# nes_controller_v2_0.net
KiCad netlist of a schematic drawn in EAGLE
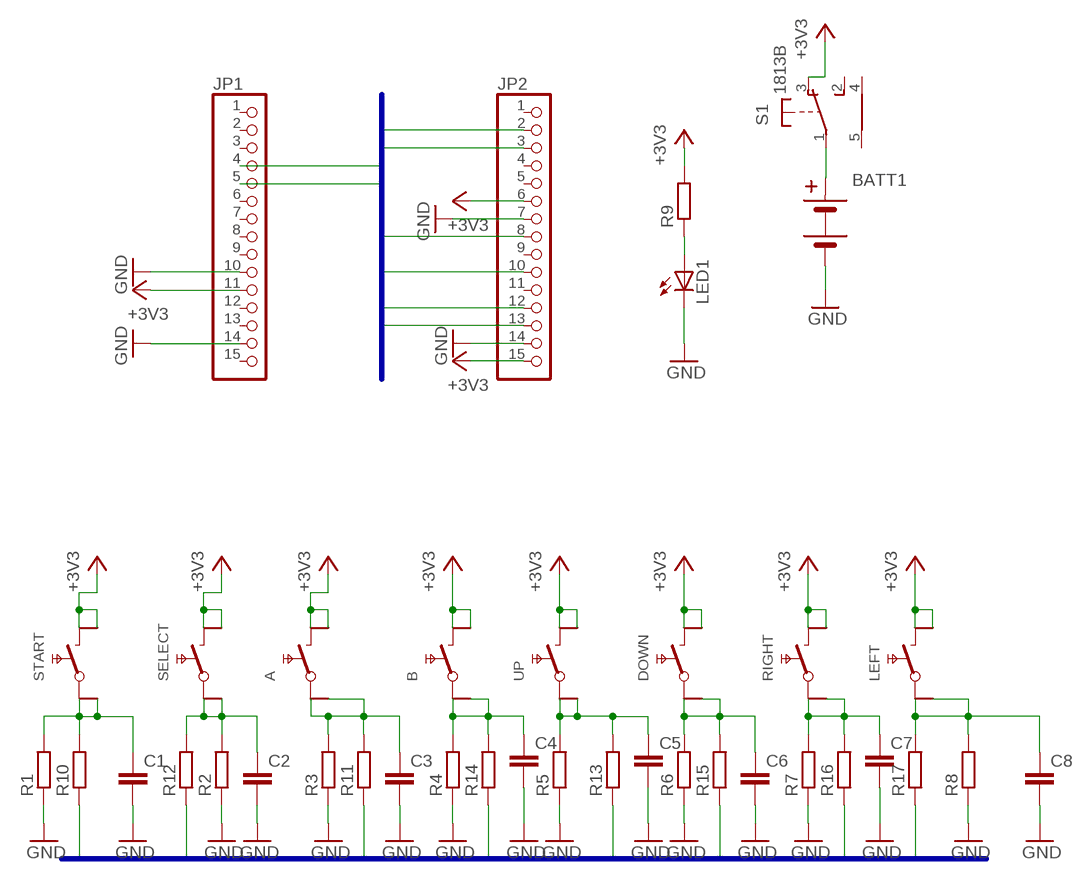
[diagram p0: schematic, sheet 1]

(export (version "E")
  (design (tool "Eeschema 10.0.6"))
  (components
    (comp (ref "A")
      (value "SMDTAST")
      (footprint "eagle-import:SMDTAST")
      (libsource (lib "eagle-import") (part "SMDTAST"))
    )
    (comp (ref "B")
      (value "SMDTAST")
      (footprint "eagle-import:SMDTAST")
      (libsource (lib "eagle-import") (part "SMDTAST"))
    )
    (comp (ref "BATT1")
      (value "BATTERIEHALTER_2X_AAA")
      (footprint "eagle-import:BATTERIEHALTER")
      (libsource (lib "eagle-import") (part "BATTERIEHALTER_2X_AAA"))
    )
    (comp (ref "C1")
      (value "C-EUC0805K")
      (footprint "eagle-import:C0805K")
      (libsource (lib "eagle-import") (part "C-EUC0805K"))
    )
    (comp (ref "C2")
      (value "C-EUC0805K")
      (footprint "eagle-import:C0805K")
      (libsource (lib "eagle-import") (part "C-EUC0805K"))
    )
    (comp (ref "C3")
      (value "C-EUC0805K")
      (footprint "eagle-import:C0805K")
      (libsource (lib "eagle-import") (part "C-EUC0805K"))
    )
    (comp (ref "C4")
      (value "C-EUC0805K")
      (footprint "eagle-import:C0805K")
      (libsource (lib "eagle-import") (part "C-EUC0805K"))
    )
    (comp (ref "C5")
      (value "C-EUC0805K")
      (footprint "eagle-import:C0805K")
      (libsource (lib "eagle-import") (part "C-EUC0805K"))
    )
    (comp (ref "C6")
      (value "C-EUC0805K")
      (footprint "eagle-import:C0805K")
      (libsource (lib "eagle-import") (part "C-EUC0805K"))
    )
    (comp (ref "C7")
      (value "C-EUC0805K")
      (footprint "eagle-import:C0805K")
      (libsource (lib "eagle-import") (part "C-EUC0805K"))
    )
    (comp (ref "C8")
      (value "C-EUC0805K")
      (footprint "eagle-import:C0805K")
      (libsource (lib "eagle-import") (part "C-EUC0805K"))
    )
    (comp (ref "DOWN")
      (value "SMDTAST")
      (footprint "eagle-import:SMDTAST")
      (libsource (lib "eagle-import") (part "SMDTAST"))
    )
    (comp (ref "JP1")
      (value "PINHD-1X15")
      (footprint "eagle-import:1X15")
      (libsource (lib "eagle-import") (part "PINHD-1X15"))
    )
    (comp (ref "JP2")
      (value "PINHD-1X15")
      (footprint "eagle-import:1X15")
      (libsource (lib "eagle-import") (part "PINHD-1X15"))
    )
    (comp (ref "LED1")
      (value "LED3MM")
      (footprint "eagle-import:LED3MM")
      (libsource (lib "eagle-import") (part "LED3MM"))
    )
    (comp (ref "LEFT")
      (value "SMDTAST")
      (footprint "eagle-import:SMDTAST")
      (libsource (lib "eagle-import") (part "SMDTAST"))
    )
    (comp (ref "R1")
      (value "R-EU_R1206")
      (footprint "eagle-import:R1206")
      (libsource (lib "eagle-import") (part "R-EU_R1206"))
    )
    (comp (ref "R2")
      (value "R-EU_R1206")
      (footprint "eagle-import:R1206")
      (libsource (lib "eagle-import") (part "R-EU_R1206"))
    )
    (comp (ref "R3")
      (value "R-EU_R1206")
      (footprint "eagle-import:R1206")
      (libsource (lib "eagle-import") (part "R-EU_R1206"))
    )
    (comp (ref "R4")
      (value "R-EU_R1206")
      (footprint "eagle-import:R1206")
      (libsource (lib "eagle-import") (part "R-EU_R1206"))
    )
    (comp (ref "R5")
      (value "R-EU_R1206")
      (footprint "eagle-import:R1206")
      (libsource (lib "eagle-import") (part "R-EU_R1206"))
    )
    (comp (ref "R6")
      (value "R-EU_R1206")
      (footprint "eagle-import:R1206")
      (libsource (lib "eagle-import") (part "R-EU_R1206"))
    )
    (comp (ref "R7")
      (value "R-EU_R1206")
      (footprint "eagle-import:R1206")
      (libsource (lib "eagle-import") (part "R-EU_R1206"))
    )
    (comp (ref "R8")
      (value "R-EU_R1206")
      (footprint "eagle-import:R1206")
      (libsource (lib "eagle-import") (part "R-EU_R1206"))
    )
    (comp (ref "R9")
      (value "R-EU_R1206")
      (footprint "eagle-import:R1206")
      (libsource (lib "eagle-import") (part "R-EU_R1206"))
    )
    (comp (ref "R10")
      (value "R-EU_R1206")
      (footprint "eagle-import:R1206")
      (libsource (lib "eagle-import") (part "R-EU_R1206"))
    )
    (comp (ref "R11")
      (value "R-EU_R1206")
      (footprint "eagle-import:R1206")
      (libsource (lib "eagle-import") (part "R-EU_R1206"))
    )
    (comp (ref "R12")
      (value "R-EU_R1206")
      (footprint "eagle-import:R1206")
      (libsource (lib "eagle-import") (part "R-EU_R1206"))
    )
    (comp (ref "R13")
      (value "R-EU_R1206")
      (footprint "eagle-import:R1206")
      (libsource (lib "eagle-import") (part "R-EU_R1206"))
    )
    (comp (ref "R14")
      (value "R-EU_R1206")
      (footprint "eagle-import:R1206")
      (libsource (lib "eagle-import") (part "R-EU_R1206"))
    )
    (comp (ref "R15")
      (value "R-EU_R1206")
      (footprint "eagle-import:R1206")
      (libsource (lib "eagle-import") (part "R-EU_R1206"))
    )
    (comp (ref "R16")
      (value "R-EU_R1206")
      (footprint "eagle-import:R1206")
      (libsource (lib "eagle-import") (part "R-EU_R1206"))
    )
    (comp (ref "R17")
      (value "R-EU_R1206")
      (footprint "eagle-import:R1206")
      (libsource (lib "eagle-import") (part "R-EU_R1206"))
    )
    (comp (ref "RIGHT")
      (value "SMDTAST")
      (footprint "eagle-import:SMDTAST")
      (libsource (lib "eagle-import") (part "SMDTAST"))
    )
    (comp (ref "S1")
      (value "1813B")
      (footprint "eagle-import:1813B")
      (libsource (lib "eagle-import") (part "1813B"))
    )
    (comp (ref "SELECT")
      (value "SMDTAST")
      (footprint "eagle-import:SMDTAST")
      (libsource (lib "eagle-import") (part "SMDTAST"))
    )
    (comp (ref "START")
      (value "SMDTAST")
      (footprint "eagle-import:SMDTAST")
      (libsource (lib "eagle-import") (part "SMDTAST"))
    )
    (comp (ref "UP")
      (value "SMDTAST")
      (footprint "eagle-import:SMDTAST")
      (libsource (lib "eagle-import") (part "SMDTAST"))
    )
  )
  (nets
    (net (code "1") (name "+3V3") (class "Default")
      (node (ref "A") (pin "2") (pinfunction "2_2") (pintype "bidirectional"))
      (node (ref "A") (pin "22") (pinfunction "22_22") (pintype "bidirectional"))
      (node (ref "B") (pin "2") (pinfunction "2_2") (pintype "bidirectional"))
      (node (ref "B") (pin "22") (pinfunction "22_22") (pintype "bidirectional"))
      (node (ref "DOWN") (pin "2") (pinfunction "2_2") (pintype "bidirectional"))
      (node (ref "DOWN") (pin "22") (pinfunction "22_22") (pintype "bidirectional"))
      (node (ref "JP1") (pin "11") (pinfunction "11_11") (pintype "passive"))
      (node (ref "JP2") (pin "15") (pinfunction "15_15") (pintype "passive"))
      (node (ref "JP2") (pin "6") (pinfunction "6_6") (pintype "passive"))
      (node (ref "LEFT") (pin "2") (pinfunction "2_2") (pintype "bidirectional"))
      (node (ref "LEFT") (pin "22") (pinfunction "22_22") (pintype "bidirectional"))
      (node (ref "R9") (pin "2") (pinfunction "2_2") (pintype "passive"))
      (node (ref "RIGHT") (pin "2") (pinfunction "2_2") (pintype "bidirectional"))
      (node (ref "RIGHT") (pin "22") (pinfunction "22_22") (pintype "bidirectional"))
      (node (ref "S1") (pin "3") (pinfunction "O_3") (pintype "passive"))
      (node (ref "SELECT") (pin "2") (pinfunction "2_2") (pintype "bidirectional"))
      (node (ref "SELECT") (pin "22") (pinfunction "22_22") (pintype "bidirectional"))
      (node (ref "START") (pin "2") (pinfunction "2_2") (pintype "bidirectional"))
      (node (ref "START") (pin "22") (pinfunction "22_22") (pintype "bidirectional"))
      (node (ref "UP") (pin "2") (pinfunction "2_2") (pintype "bidirectional"))
      (node (ref "UP") (pin "22") (pinfunction "22_22") (pintype "bidirectional"))
    )
    (net (code "2") (name "/A") (class "Default")
      (node (ref "JP1") (pin "5") (pinfunction "5_5") (pintype "passive"))
      (node (ref "R11") (pin "1") (pinfunction "1_1") (pintype "passive"))
    )
    (net (code "3") (name "/B") (class "Default")
      (node (ref "JP1") (pin "4") (pinfunction "4_4") (pintype "passive"))
      (node (ref "R14") (pin "1") (pinfunction "1_1") (pintype "passive"))
    )
    (net (code "4") (name "/DOWN") (class "Default")
      (node (ref "JP2") (pin "10") (pinfunction "10_10") (pintype "passive"))
      (node (ref "R15") (pin "1") (pinfunction "1_1") (pintype "passive"))
    )
    (net (code "5") (name "/LEFT") (class "Default")
      (node (ref "JP2") (pin "3") (pinfunction "3_3") (pintype "passive"))
      (node (ref "R17") (pin "1") (pinfunction "1_1") (pintype "passive"))
    )
    (net (code "6") (name "/RIGHT") (class "Default")
      (node (ref "JP2") (pin "8") (pinfunction "8_8") (pintype "passive"))
      (node (ref "R16") (pin "1") (pinfunction "1_1") (pintype "passive"))
    )
    (net (code "7") (name "/SELECT") (class "Default")
      (node (ref "JP2") (pin "12") (pinfunction "12_12") (pintype "passive"))
      (node (ref "R12") (pin "1") (pinfunction "1_1") (pintype "passive"))
    )
    (net (code "8") (name "/START") (class "Default")
      (node (ref "JP2") (pin "13") (pinfunction "13_13") (pintype "passive"))
      (node (ref "R10") (pin "1") (pinfunction "1_1") (pintype "passive"))
    )
    (net (code "9") (name "/UP") (class "Default")
      (node (ref "JP2") (pin "2") (pinfunction "2_2") (pintype "passive"))
      (node (ref "R13") (pin "1") (pinfunction "1_1") (pintype "passive"))
    )
    (net (code "11") (name "GND") (class "Default")
      (node (ref "BATT1") (pin "P-") (pinfunction "P-_P-") (pintype "bidirectional"))
      (node (ref "C1") (pin "2") (pinfunction "2_2") (pintype "passive"))
      (node (ref "C2") (pin "2") (pinfunction "2_2") (pintype "passive"))
      (node (ref "C3") (pin "2") (pinfunction "2_2") (pintype "passive"))
      (node (ref "C4") (pin "2") (pinfunction "2_2") (pintype "passive"))
      (node (ref "C5") (pin "2") (pinfunction "2_2") (pintype "passive"))
      (node (ref "C6") (pin "2") (pinfunction "2_2") (pintype "passive"))
      (node (ref "C7") (pin "2") (pinfunction "2_2") (pintype "passive"))
      (node (ref "C8") (pin "2") (pinfunction "2_2") (pintype "passive"))
      (node (ref "JP1") (pin "10") (pinfunction "10_10") (pintype "passive"))
      (node (ref "JP1") (pin "14") (pinfunction "14_14") (pintype "passive"))
      (node (ref "JP2") (pin "14") (pinfunction "14_14") (pintype "passive"))
      (node (ref "JP2") (pin "7") (pinfunction "7_7") (pintype "passive"))
      (node (ref "LED1") (pin "K") (pinfunction "C_K") (pintype "passive"))
      (node (ref "R1") (pin "1") (pinfunction "1_1") (pintype "passive"))
      (node (ref "R2") (pin "1") (pinfunction "1_1") (pintype "passive"))
      (node (ref "R3") (pin "1") (pinfunction "1_1") (pintype "passive"))
      (node (ref "R4") (pin "1") (pinfunction "1_1") (pintype "passive"))
      (node (ref "R5") (pin "1") (pinfunction "1_1") (pintype "passive"))
      (node (ref "R6") (pin "1") (pinfunction "1_1") (pintype "passive"))
      (node (ref "R7") (pin "1") (pinfunction "1_1") (pintype "passive"))
      (node (ref "R8") (pin "1") (pinfunction "1_1") (pintype "passive"))
    )
    (net (code "12") (name "Net-(A-Pad1)") (class "Default")
      (node (ref "A") (pin "1") (pinfunction "1_1") (pintype "bidirectional"))
      (node (ref "A") (pin "11") (pinfunction "11_11") (pintype "bidirectional"))
      (node (ref "C3") (pin "1") (pinfunction "1_1") (pintype "passive"))
      (node (ref "R11") (pin "2") (pinfunction "2_2") (pintype "passive"))
      (node (ref "R3") (pin "2") (pinfunction "2_2") (pintype "passive"))
    )
    (net (code "13") (name "Net-(B-Pad1)") (class "Default")
      (node (ref "B") (pin "1") (pinfunction "1_1") (pintype "bidirectional"))
      (node (ref "B") (pin "11") (pinfunction "11_11") (pintype "bidirectional"))
      (node (ref "C4") (pin "1") (pinfunction "1_1") (pintype "passive"))
      (node (ref "R14") (pin "2") (pinfunction "2_2") (pintype "passive"))
      (node (ref "R4") (pin "2") (pinfunction "2_2") (pintype "passive"))
    )
    (net (code "14") (name "Net-(C1-Pad1)") (class "Default")
      (node (ref "C1") (pin "1") (pinfunction "1_1") (pintype "passive"))
      (node (ref "R1") (pin "2") (pinfunction "2_2") (pintype "passive"))
      (node (ref "R10") (pin "2") (pinfunction "2_2") (pintype "passive"))
      (node (ref "START") (pin "1") (pinfunction "1_1") (pintype "bidirectional"))
      (node (ref "START") (pin "11") (pinfunction "11_11") (pintype "bidirectional"))
    )
    (net (code "15") (name "Net-(C2-Pad1)") (class "Default")
      (node (ref "C2") (pin "1") (pinfunction "1_1") (pintype "passive"))
      (node (ref "R12") (pin "2") (pinfunction "2_2") (pintype "passive"))
      (node (ref "R2") (pin "2") (pinfunction "2_2") (pintype "passive"))
      (node (ref "SELECT") (pin "1") (pinfunction "1_1") (pintype "bidirectional"))
      (node (ref "SELECT") (pin "11") (pinfunction "11_11") (pintype "bidirectional"))
    )
    (net (code "16") (name "Net-(C5-Pad1)") (class "Default")
      (node (ref "C5") (pin "1") (pinfunction "1_1") (pintype "passive"))
      (node (ref "R13") (pin "2") (pinfunction "2_2") (pintype "passive"))
      (node (ref "R5") (pin "2") (pinfunction "2_2") (pintype "passive"))
      (node (ref "UP") (pin "1") (pinfunction "1_1") (pintype "bidirectional"))
      (node (ref "UP") (pin "11") (pinfunction "11_11") (pintype "bidirectional"))
    )
    (net (code "17") (name "Net-(C6-Pad1)") (class "Default")
      (node (ref "C6") (pin "1") (pinfunction "1_1") (pintype "passive"))
      (node (ref "DOWN") (pin "1") (pinfunction "1_1") (pintype "bidirectional"))
      (node (ref "DOWN") (pin "11") (pinfunction "11_11") (pintype "bidirectional"))
      (node (ref "R15") (pin "2") (pinfunction "2_2") (pintype "passive"))
      (node (ref "R6") (pin "2") (pinfunction "2_2") (pintype "passive"))
    )
    (net (code "18") (name "Net-(C7-Pad1)") (class "Default")
      (node (ref "C7") (pin "1") (pinfunction "1_1") (pintype "passive"))
      (node (ref "R16") (pin "2") (pinfunction "2_2") (pintype "passive"))
      (node (ref "R7") (pin "2") (pinfunction "2_2") (pintype "passive"))
      (node (ref "RIGHT") (pin "1") (pinfunction "1_1") (pintype "bidirectional"))
      (node (ref "RIGHT") (pin "11") (pinfunction "11_11") (pintype "bidirectional"))
    )
    (net (code "19") (name "Net-(C8-Pad1)") (class "Default")
      (node (ref "C8") (pin "1") (pinfunction "1_1") (pintype "passive"))
      (node (ref "LEFT") (pin "1") (pinfunction "1_1") (pintype "bidirectional"))
      (node (ref "LEFT") (pin "11") (pinfunction "11_11") (pintype "bidirectional"))
      (node (ref "R17") (pin "2") (pinfunction "2_2") (pintype "passive"))
      (node (ref "R8") (pin "2") (pinfunction "2_2") (pintype "passive"))
    )
    (net (code "20") (name "Net-(LED1-PadA)") (class "Default")
      (node (ref "LED1") (pin "A") (pinfunction "A_A") (pintype "passive"))
      (node (ref "R9") (pin "1") (pinfunction "1_1") (pintype "passive"))
    )
    (net (code "21") (name "Net-(S1-W)") (class "Default")
      (node (ref "BATT1") (pin "P+") (pinfunction "P+_P+") (pintype "bidirectional"))
      (node (ref "S1") (pin "1") (pinfunction "W_1") (pintype "passive"))
    )
    (net (code "22") (name "unconnected-(JP1-Pad1)") (class "Default")
      (node (ref "JP1") (pin "1") (pinfunction "1_1") (pintype "passive"))
    )
    (net (code "23") (name "unconnected-(JP1-Pad2)") (class "Default")
      (node (ref "JP1") (pin "2") (pinfunction "2_2") (pintype "passive"))
    )
    (net (code "24") (name "unconnected-(JP1-Pad3)") (class "Default")
      (node (ref "JP1") (pin "3") (pinfunction "3_3") (pintype "passive"))
    )
    (net (code "25") (name "unconnected-(JP1-Pad6)") (class "Default")
      (node (ref "JP1") (pin "6") (pinfunction "6_6") (pintype "passive"))
    )
    (net (code "26") (name "unconnected-(JP1-Pad7)") (class "Default")
      (node (ref "JP1") (pin "7") (pinfunction "7_7") (pintype "passive"))
    )
    (net (code "27") (name "unconnected-(JP1-Pad8)") (class "Default")
      (node (ref "JP1") (pin "8") (pinfunction "8_8") (pintype "passive"))
    )
    (net (code "28") (name "unconnected-(JP1-Pad9)") (class "Default")
      (node (ref "JP1") (pin "9") (pinfunction "9_9") (pintype "passive"))
    )
    (net (code "29") (name "unconnected-(JP1-Pad12)") (class "Default")
      (node (ref "JP1") (pin "12") (pinfunction "12_12") (pintype "passive"))
    )
    (net (code "30") (name "unconnected-(JP1-Pad13)") (class "Default")
      (node (ref "JP1") (pin "13") (pinfunction "13_13") (pintype "passive"))
    )
    (net (code "31") (name "unconnected-(JP1-Pad15)") (class "Default")
      (node (ref "JP1") (pin "15") (pinfunction "15_15") (pintype "passive"))
    )
    (net (code "32") (name "unconnected-(JP2-Pad1)") (class "Default")
      (node (ref "JP2") (pin "1") (pinfunction "1_1") (pintype "passive"))
    )
    (net (code "33") (name "unconnected-(JP2-Pad4)") (class "Default")
      (node (ref "JP2") (pin "4") (pinfunction "4_4") (pintype "passive"))
    )
    (net (code "34") (name "unconnected-(JP2-Pad5)") (class "Default")
      (node (ref "JP2") (pin "5") (pinfunction "5_5") (pintype "passive"))
    )
    (net (code "35") (name "unconnected-(JP2-Pad9)") (class "Default")
      (node (ref "JP2") (pin "9") (pinfunction "9_9") (pintype "passive"))
    )
    (net (code "36") (name "unconnected-(JP2-Pad11)") (class "Default")
      (node (ref "JP2") (pin "11") (pinfunction "11_11") (pintype "passive"))
    )
    (net (code "37") (name "unconnected-(S1-S-Pad2)") (class "Default")
      (node (ref "S1") (pin "2") (pinfunction "S_2") (pintype "passive"))
    )
    (net (code "38") (name "unconnected-(S1-SH1-Pad4)") (class "Default")
      (node (ref "S1") (pin "4") (pinfunction "SH1_4") (pintype "passive"))
    )
    (net (code "39") (name "unconnected-(S1-SH2-Pad5)") (class "Default")
      (node (ref "S1") (pin "5") (pinfunction "SH2_5") (pintype "passive"))
    )
  )
)
